# hand_pcb.net
KiCad netlist of a schematic drawn in EAGLE
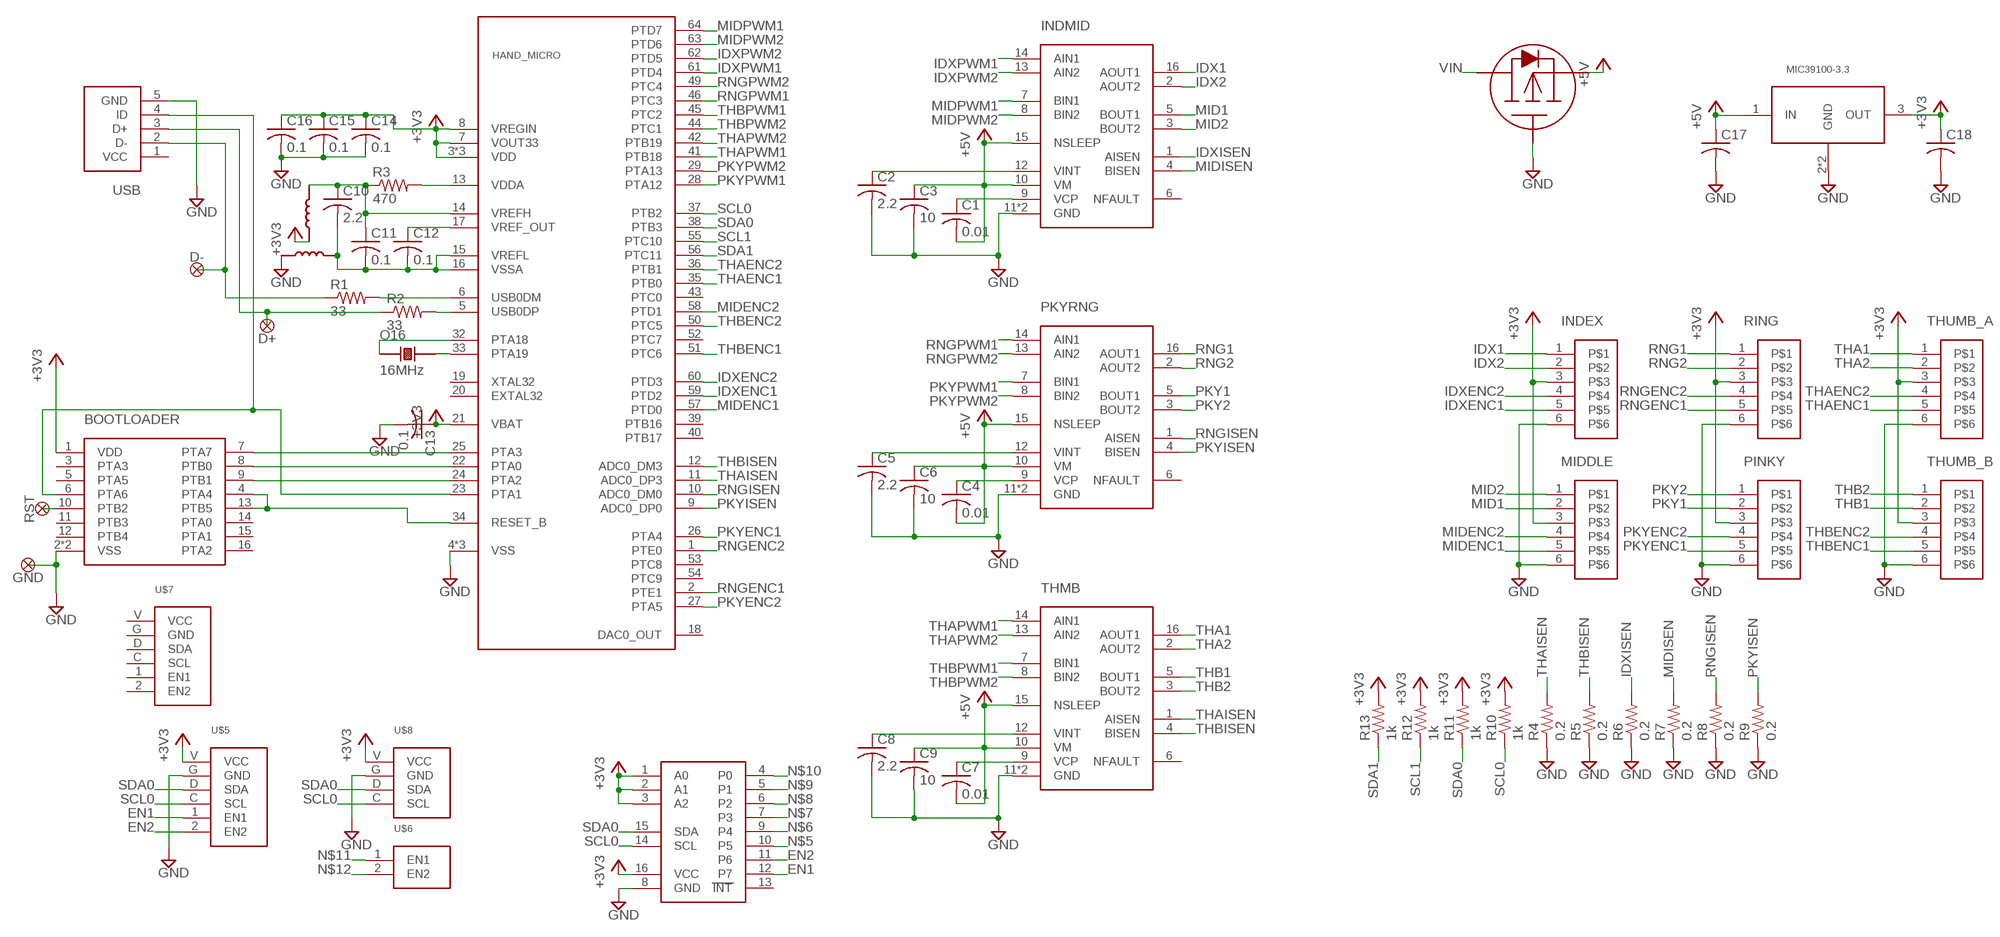
[diagram p0: schematic, sheet 1]

(export (version "E")
  (design (tool "Eeschema 10.0.6"))
  (components
    (comp (ref "BOOTLOADER")
      (value "MKL02Z32")
      (footprint "eagle-import:WQFN-16")
      (libsource (lib "eagle-import") (part "MKL02Z32"))
    )
    (comp (ref "C1")
      (value "0.01")
      (footprint "eagle-import:C0603")
      (libsource (lib "eagle-import") (part "C-USC0603"))
    )
    (comp (ref "C2")
      (value "2.2")
      (footprint "eagle-import:C0603")
      (libsource (lib "eagle-import") (part "C-USC0603"))
    )
    (comp (ref "C3")
      (value "10")
      (footprint "eagle-import:C0603")
      (libsource (lib "eagle-import") (part "C-USC0603"))
    )
    (comp (ref "C4")
      (value "0.01")
      (footprint "eagle-import:C0603")
      (libsource (lib "eagle-import") (part "C-USC0603"))
    )
    (comp (ref "C5")
      (value "2.2")
      (footprint "eagle-import:C0603")
      (libsource (lib "eagle-import") (part "C-USC0603"))
    )
    (comp (ref "C6")
      (value "10")
      (footprint "eagle-import:C0603")
      (libsource (lib "eagle-import") (part "C-USC0603"))
    )
    (comp (ref "C7")
      (value "0.01")
      (footprint "eagle-import:C0603")
      (libsource (lib "eagle-import") (part "C-USC0603"))
    )
    (comp (ref "C8")
      (value "2.2")
      (footprint "eagle-import:C0603")
      (libsource (lib "eagle-import") (part "C-USC0603"))
    )
    (comp (ref "C9")
      (value "10")
      (footprint "eagle-import:C0603")
      (libsource (lib "eagle-import") (part "C-USC0603"))
    )
    (comp (ref "C10")
      (value "2.2")
      (footprint "eagle-import:C0402")
      (libsource (lib "eagle-import") (part "C-USC0402"))
    )
    (comp (ref "C11")
      (value "0.1")
      (footprint "eagle-import:C0402")
      (libsource (lib "eagle-import") (part "C-USC0402"))
    )
    (comp (ref "C12")
      (value "0.1")
      (footprint "eagle-import:C0402")
      (libsource (lib "eagle-import") (part "C-USC0402"))
    )
    (comp (ref "C13")
      (value "0.1")
      (footprint "eagle-import:C0402")
      (libsource (lib "eagle-import") (part "C-USC0402"))
    )
    (comp (ref "C14")
      (value "0.1")
      (footprint "eagle-import:C0402")
      (libsource (lib "eagle-import") (part "C-USC0402"))
    )
    (comp (ref "C15")
      (value "0.1")
      (footprint "eagle-import:C0402")
      (libsource (lib "eagle-import") (part "C-USC0402"))
    )
    (comp (ref "C16")
      (value "0.1")
      (footprint "eagle-import:C0402")
      (libsource (lib "eagle-import") (part "C-USC0402"))
    )
    (comp (ref "C17")
      (value "C-USC0603")
      (footprint "eagle-import:C0603")
      (libsource (lib "eagle-import") (part "C-USC0603"))
    )
    (comp (ref "C18")
      (value "C-USC0603")
      (footprint "eagle-import:C0603")
      (libsource (lib "eagle-import") (part "C-USC0603"))
    )
    (comp (ref "D+")
      (value "TESTPAD")
      (footprint "eagle-import:TESTPAD")
      (libsource (lib "eagle-import") (part "TESTPAD"))
    )
    (comp (ref "D-")
      (value "TESTPAD")
      (footprint "eagle-import:TESTPAD")
      (libsource (lib "eagle-import") (part "TESTPAD"))
    )
    (comp (ref "GND")
      (value "TESTPAD")
      (footprint "eagle-import:TESTPAD")
      (libsource (lib "eagle-import") (part "TESTPAD"))
    )
    (comp (ref "HAND_MICRO")
      (value "MK20DX256VLH7")
      (footprint "eagle-import:LQFP-64-10-10")
      (libsource (lib "eagle-import") (part "MK20DX256VLH7"))
    )
    (comp (ref "INDEX")
      (value "DF57H-6PTOP")
      (footprint "eagle-import:DF57H-6P-TOP")
      (libsource (lib "eagle-import") (part "DF57H-6PTOP"))
    )
    (comp (ref "INDMID")
      (value "DRV8833")
      (footprint "eagle-import:WQFN-16")
      (libsource (lib "eagle-import") (part "DRV8833"))
    )
    (comp (ref "MIDDLE")
      (value "DF57H-6PTOP")
      (footprint "eagle-import:DF57H-6P-TOP")
      (libsource (lib "eagle-import") (part "DF57H-6PTOP"))
    )
    (comp (ref "O16")
      (value "16MHz")
      (footprint "eagle-import:NX3225SA")
      (libsource (lib "eagle-import") (part "NX3225SA"))
    )
    (comp (ref "PINKY")
      (value "DF57H-6PTOP")
      (footprint "eagle-import:DF57H-6P-TOP")
      (libsource (lib "eagle-import") (part "DF57H-6PTOP"))
    )
    (comp (ref "PKYRNG")
      (value "DRV8833")
      (footprint "eagle-import:WQFN-16")
      (libsource (lib "eagle-import") (part "DRV8833"))
    )
    (comp (ref "R1")
      (value "33")
      (footprint "eagle-import:R0402")
      (libsource (lib "eagle-import") (part "R-US_R0402"))
    )
    (comp (ref "R2")
      (value "33")
      (footprint "eagle-import:R0402")
      (libsource (lib "eagle-import") (part "R-US_R0402"))
    )
    (comp (ref "R3")
      (value "470")
      (footprint "eagle-import:R0402")
      (libsource (lib "eagle-import") (part "R-US_R0402"))
    )
    (comp (ref "R4")
      (value "0.2")
      (footprint "eagle-import:R1206")
      (libsource (lib "eagle-import") (part "R-US_R1206"))
    )
    (comp (ref "R5")
      (value "0.2")
      (footprint "eagle-import:R1206")
      (libsource (lib "eagle-import") (part "R-US_R1206"))
    )
    (comp (ref "R6")
      (value "0.2")
      (footprint "eagle-import:R1206")
      (libsource (lib "eagle-import") (part "R-US_R1206"))
    )
    (comp (ref "R7")
      (value "0.2")
      (footprint "eagle-import:R1206")
      (libsource (lib "eagle-import") (part "R-US_R1206"))
    )
    (comp (ref "R8")
      (value "0.2")
      (footprint "eagle-import:R1206")
      (libsource (lib "eagle-import") (part "R-US_R1206"))
    )
    (comp (ref "R9")
      (value "0.2")
      (footprint "eagle-import:R1206")
      (libsource (lib "eagle-import") (part "R-US_R1206"))
    )
    (comp (ref "R10")
      (value "1k")
      (footprint "eagle-import:R0603")
      (libsource (lib "eagle-import") (part "R-US_R0603"))
    )
    (comp (ref "R11")
      (value "1k")
      (footprint "eagle-import:R0603")
      (libsource (lib "eagle-import") (part "R-US_R0603"))
    )
    (comp (ref "R12")
      (value "1k")
      (footprint "eagle-import:R0603")
      (libsource (lib "eagle-import") (part "R-US_R0603"))
    )
    (comp (ref "R13")
      (value "1k")
      (footprint "eagle-import:R0603")
      (libsource (lib "eagle-import") (part "R-US_R0603"))
    )
    (comp (ref "RING")
      (value "DF57H-6PTOP")
      (footprint "eagle-import:DF57H-6P-TOP")
      (libsource (lib "eagle-import") (part "DF57H-6PTOP"))
    )
    (comp (ref "RST")
      (value "TESTPAD")
      (footprint "eagle-import:TESTPAD")
      (libsource (lib "eagle-import") (part "TESTPAD"))
    )
    (comp (ref "THMB")
      (value "DRV8833")
      (footprint "eagle-import:WQFN-16")
      (libsource (lib "eagle-import") (part "DRV8833"))
    )
    (comp (ref "THUMB_A")
      (value "DF57H-6PTOP")
      (footprint "eagle-import:DF57H-6P-TOP")
      (libsource (lib "eagle-import") (part "DF57H-6PTOP"))
    )
    (comp (ref "THUMB_B")
      (value "DF57H-6PTOP")
      (footprint "eagle-import:DF57H-6P-TOP")
      (libsource (lib "eagle-import") (part "DF57H-6PTOP"))
    )
    (comp (ref "U$1")
      (value "TCA9534TSSOP")
      (footprint "eagle-import:TSSOP16")
      (libsource (lib "eagle-import") (part "TCA9534TSSOP"))
    )
    (comp (ref "U$2")
      (value "SPD15P10PLG")
      (footprint "eagle-import:PG-TO-252-3")
      (libsource (lib "eagle-import") (part "SPD15P10PLG"))
    )
    (comp (ref "U$3")
      (value "FERRITE600OHM100MHZ")
      (footprint "eagle-import:L0603")
      (libsource (lib "eagle-import") (part "FERRITE600OHM100MHZ"))
    )
    (comp (ref "U$4")
      (value "FERRITE600OHM100MHZ")
      (footprint "eagle-import:L0603")
      (libsource (lib "eagle-import") (part "FERRITE600OHM100MHZ"))
    )
    (comp (ref "U$5")
      (value "PSENSE")
      (footprint "eagle-import:PSENSE")
      (libsource (lib "eagle-import") (part "PSENSE"))
    )
    (comp (ref "U$6")
      (value "PSENSE2")
      (footprint "eagle-import:PSENSE2")
      (libsource (lib "eagle-import") (part "PSENSE2"))
    )
    (comp (ref "U$7")
      (value "PSENSE")
      (footprint "eagle-import:PSENSE")
      (libsource (lib "eagle-import") (part "PSENSE"))
    )
    (comp (ref "U$8")
      (value "PSENSE4")
      (footprint "eagle-import:PSENSE4")
      (libsource (lib "eagle-import") (part "PSENSE4"))
    )
    (comp (ref "U$9")
      (value "MIC391003.3")
      (footprint "eagle-import:MIC39100")
      (libsource (lib "eagle-import") (part "MIC391003.3"))
    )
    (comp (ref "USB")
      (value "10118194-0001LF")
      (footprint "eagle-import:10118194-0001LF")
      (libsource (lib "eagle-import") (part "10118194-0001LF"))
    )
  )
  (nets
    (net (code "1") (name "+3V3") (class "Default")
      (node (ref "BOOTLOADER") (pin "1") (pinfunction "VDD_1") (pintype "bidirectional"))
      (node (ref "C13") (pin "1") (pinfunction "1_1") (pintype "passive"))
      (node (ref "C14") (pin "1") (pinfunction "1_1") (pintype "passive"))
      (node (ref "C15") (pin "1") (pinfunction "1_1") (pintype "passive"))
      (node (ref "C16") (pin "1") (pinfunction "1_1") (pintype "passive"))
      (node (ref "C18") (pin "1") (pinfunction "1_1") (pintype "passive"))
      (node (ref "HAND_MICRO") (pin "21") (pinfunction "VBAT_21") (pintype "bidirectional"))
      (node (ref "HAND_MICRO") (pin "3") (pinfunction "VDD_3") (pintype "bidirectional"))
      (node (ref "HAND_MICRO") (pin "30") (pinfunction "VDD_30") (pintype "bidirectional"))
      (node (ref "HAND_MICRO") (pin "48") (pinfunction "VDD_48") (pintype "bidirectional"))
      (node (ref "HAND_MICRO") (pin "7") (pinfunction "VOUT33_7") (pintype "bidirectional"))
      (node (ref "HAND_MICRO") (pin "8") (pinfunction "VREGIN_8") (pintype "bidirectional"))
      (node (ref "INDEX") (pin "3") (pinfunction "P$3_3") (pintype "bidirectional"))
      (node (ref "MIDDLE") (pin "3") (pinfunction "P$3_3") (pintype "bidirectional"))
      (node (ref "PINKY") (pin "3") (pinfunction "P$3_3") (pintype "bidirectional"))
      (node (ref "R10") (pin "2") (pinfunction "2_2") (pintype "passive"))
      (node (ref "R11") (pin "2") (pinfunction "2_2") (pintype "passive"))
      (node (ref "R12") (pin "2") (pinfunction "2_2") (pintype "passive"))
      (node (ref "R13") (pin "2") (pinfunction "2_2") (pintype "passive"))
      (node (ref "RING") (pin "3") (pinfunction "P$3_3") (pintype "bidirectional"))
      (node (ref "THUMB_A") (pin "3") (pinfunction "P$3_3") (pintype "bidirectional"))
      (node (ref "THUMB_B") (pin "3") (pinfunction "P$3_3") (pintype "bidirectional"))
      (node (ref "U$1") (pin "1") (pinfunction "A0_1") (pintype "bidirectional"))
      (node (ref "U$1") (pin "16") (pinfunction "VCC_16") (pintype "bidirectional"))
      (node (ref "U$1") (pin "2") (pinfunction "A1_2") (pintype "bidirectional"))
      (node (ref "U$1") (pin "3") (pinfunction "A2_3") (pintype "bidirectional"))
      (node (ref "U$4") (pin "1") (pinfunction "P$1_1") (pintype "bidirectional"))
      (node (ref "U$5") (pin "V") (pinfunction "VCC_V") (pintype "bidirectional"))
      (node (ref "U$8") (pin "V") (pinfunction "VCC_V") (pintype "bidirectional"))
      (node (ref "U$9") (pin "3") (pinfunction "OUT_3") (pintype "bidirectional"))
    )
    (net (code "2") (name "+5V") (class "Default")
      (node (ref "C1") (pin "2") (pinfunction "2_2") (pintype "passive"))
      (node (ref "C17") (pin "1") (pinfunction "1_1") (pintype "passive"))
      (node (ref "C3") (pin "1") (pinfunction "1_1") (pintype "passive"))
      (node (ref "C4") (pin "2") (pinfunction "2_2") (pintype "passive"))
      (node (ref "C6") (pin "1") (pinfunction "1_1") (pintype "passive"))
      (node (ref "C7") (pin "2") (pinfunction "2_2") (pintype "passive"))
      (node (ref "C9") (pin "1") (pinfunction "1_1") (pintype "passive"))
      (node (ref "INDMID") (pin "10") (pinfunction "VM_10") (pintype "bidirectional"))
      (node (ref "INDMID") (pin "15") (pinfunction "NSLEEP_15") (pintype "bidirectional"))
      (node (ref "PKYRNG") (pin "10") (pinfunction "VM_10") (pintype "bidirectional"))
      (node (ref "PKYRNG") (pin "15") (pinfunction "NSLEEP_15") (pintype "bidirectional"))
      (node (ref "THMB") (pin "10") (pinfunction "VM_10") (pintype "bidirectional"))
      (node (ref "THMB") (pin "15") (pinfunction "NSLEEP_15") (pintype "bidirectional"))
      (node (ref "U$2") (pin "3") (pinfunction "3_3") (pintype "bidirectional"))
      (node (ref "U$9") (pin "1") (pinfunction "IN_1") (pintype "bidirectional"))
    )
    (net (code "3") (name "/EN1") (class "Default")
      (node (ref "U$1") (pin "12") (pinfunction "P7_12") (pintype "bidirectional"))
      (node (ref "U$5") (pin "1") (pinfunction "EN1_1") (pintype "bidirectional"))
    )
    (net (code "4") (name "/EN2") (class "Default")
      (node (ref "U$1") (pin "11") (pinfunction "P6_11") (pintype "bidirectional"))
      (node (ref "U$5") (pin "2") (pinfunction "EN2_2") (pintype "bidirectional"))
    )
    (net (code "5") (name "/IDX1") (class "Default")
      (node (ref "INDEX") (pin "1") (pinfunction "P$1_1") (pintype "bidirectional"))
      (node (ref "INDMID") (pin "16") (pinfunction "AOUT1_16") (pintype "bidirectional"))
    )
    (net (code "6") (name "/IDX2") (class "Default")
      (node (ref "INDEX") (pin "2") (pinfunction "P$2_2") (pintype "bidirectional"))
      (node (ref "INDMID") (pin "2") (pinfunction "AOUT2_2") (pintype "bidirectional"))
    )
    (net (code "7") (name "/IDXENC1") (class "Default")
      (node (ref "HAND_MICRO") (pin "59") (pinfunction "PTD2_59") (pintype "bidirectional"))
      (node (ref "INDEX") (pin "5") (pinfunction "P$5_5") (pintype "bidirectional"))
    )
    (net (code "8") (name "/IDXENC2") (class "Default")
      (node (ref "HAND_MICRO") (pin "60") (pinfunction "PTD3_60") (pintype "bidirectional"))
      (node (ref "INDEX") (pin "4") (pinfunction "P$4_4") (pintype "bidirectional"))
    )
    (net (code "9") (name "/IDXISEN") (class "Default")
      (node (ref "INDMID") (pin "1") (pinfunction "AISEN_1") (pintype "bidirectional"))
      (node (ref "R6") (pin "2") (pinfunction "2_2") (pintype "passive"))
    )
    (net (code "10") (name "/IDXPWM1") (class "Default")
      (node (ref "HAND_MICRO") (pin "61") (pinfunction "PTD4_61") (pintype "bidirectional"))
      (node (ref "INDMID") (pin "14") (pinfunction "AIN1_14") (pintype "bidirectional"))
    )
    (net (code "11") (name "/IDXPWM2") (class "Default")
      (node (ref "HAND_MICRO") (pin "62") (pinfunction "PTD5_62") (pintype "bidirectional"))
      (node (ref "INDMID") (pin "13") (pinfunction "AIN2_13") (pintype "bidirectional"))
    )
    (net (code "12") (name "/MID1") (class "Default")
      (node (ref "INDMID") (pin "5") (pinfunction "BOUT1_5") (pintype "bidirectional"))
      (node (ref "MIDDLE") (pin "2") (pinfunction "P$2_2") (pintype "bidirectional"))
    )
    (net (code "13") (name "/MID2") (class "Default")
      (node (ref "INDMID") (pin "3") (pinfunction "BOUT2_3") (pintype "bidirectional"))
      (node (ref "MIDDLE") (pin "1") (pinfunction "P$1_1") (pintype "bidirectional"))
    )
    (net (code "14") (name "/MIDENC1") (class "Default")
      (node (ref "HAND_MICRO") (pin "57") (pinfunction "PTD0_57") (pintype "bidirectional"))
      (node (ref "MIDDLE") (pin "5") (pinfunction "P$5_5") (pintype "bidirectional"))
    )
    (net (code "15") (name "/MIDENC2") (class "Default")
      (node (ref "HAND_MICRO") (pin "58") (pinfunction "PTD1_58") (pintype "bidirectional"))
      (node (ref "MIDDLE") (pin "4") (pinfunction "P$4_4") (pintype "bidirectional"))
    )
    (net (code "16") (name "/MIDISEN") (class "Default")
      (node (ref "INDMID") (pin "4") (pinfunction "BISEN_4") (pintype "bidirectional"))
      (node (ref "R7") (pin "2") (pinfunction "2_2") (pintype "passive"))
    )
    (net (code "17") (name "/MIDPWM1") (class "Default")
      (node (ref "HAND_MICRO") (pin "64") (pinfunction "PTD7_64") (pintype "bidirectional"))
      (node (ref "INDMID") (pin "7") (pinfunction "BIN1_7") (pintype "bidirectional"))
    )
    (net (code "18") (name "/MIDPWM2") (class "Default")
      (node (ref "HAND_MICRO") (pin "63") (pinfunction "PTD6_63") (pintype "bidirectional"))
      (node (ref "INDMID") (pin "8") (pinfunction "BIN2_8") (pintype "bidirectional"))
    )
    (net (code "19") (name "/N$5") (class "Default")
      (node (ref "U$1") (pin "10") (pinfunction "P5_10") (pintype "bidirectional"))
    )
    (net (code "20") (name "/N$6") (class "Default")
      (node (ref "U$1") (pin "9") (pinfunction "P4_9") (pintype "bidirectional"))
    )
    (net (code "21") (name "/N$7") (class "Default")
      (node (ref "U$1") (pin "7") (pinfunction "P3_7") (pintype "bidirectional"))
    )
    (net (code "22") (name "/N$8") (class "Default")
      (node (ref "U$1") (pin "6") (pinfunction "P2_6") (pintype "bidirectional"))
    )
    (net (code "23") (name "/N$9") (class "Default")
      (node (ref "U$1") (pin "5") (pinfunction "P1_5") (pintype "bidirectional"))
    )
    (net (code "24") (name "/N$10") (class "Default")
      (node (ref "U$1") (pin "4") (pinfunction "P0_4") (pintype "bidirectional"))
    )
    (net (code "25") (name "/N$11") (class "Default")
      (node (ref "U$6") (pin "1") (pinfunction "EN1_1") (pintype "bidirectional"))
    )
    (net (code "26") (name "/N$12") (class "Default")
      (node (ref "U$6") (pin "2") (pinfunction "EN2_2") (pintype "bidirectional"))
    )
    (net (code "27") (name "/PKY1") (class "Default")
      (node (ref "PINKY") (pin "2") (pinfunction "P$2_2") (pintype "bidirectional"))
      (node (ref "PKYRNG") (pin "5") (pinfunction "BOUT1_5") (pintype "bidirectional"))
    )
    (net (code "28") (name "/PKY2") (class "Default")
      (node (ref "PINKY") (pin "1") (pinfunction "P$1_1") (pintype "bidirectional"))
      (node (ref "PKYRNG") (pin "3") (pinfunction "BOUT2_3") (pintype "bidirectional"))
    )
    (net (code "29") (name "/PKYENC1") (class "Default")
      (node (ref "HAND_MICRO") (pin "26") (pinfunction "PTA4_26") (pintype "bidirectional"))
      (node (ref "PINKY") (pin "5") (pinfunction "P$5_5") (pintype "bidirectional"))
    )
    (net (code "30") (name "/PKYENC2") (class "Default")
      (node (ref "HAND_MICRO") (pin "27") (pinfunction "PTA5_27") (pintype "bidirectional"))
      (node (ref "PINKY") (pin "4") (pinfunction "P$4_4") (pintype "bidirectional"))
    )
    (net (code "31") (name "/PKYISEN") (class "Default")
      (node (ref "HAND_MICRO") (pin "9") (pinfunction "ADC0_DP0_9") (pintype "bidirectional"))
      (node (ref "PKYRNG") (pin "4") (pinfunction "BISEN_4") (pintype "bidirectional"))
      (node (ref "R9") (pin "2") (pinfunction "2_2") (pintype "passive"))
    )
    (net (code "32") (name "/PKYPWM1") (class "Default")
      (node (ref "HAND_MICRO") (pin "28") (pinfunction "PTA12_28") (pintype "bidirectional"))
      (node (ref "PKYRNG") (pin "7") (pinfunction "BIN1_7") (pintype "bidirectional"))
    )
    (net (code "33") (name "/PKYPWM2") (class "Default")
      (node (ref "HAND_MICRO") (pin "29") (pinfunction "PTA13_29") (pintype "bidirectional"))
      (node (ref "PKYRNG") (pin "8") (pinfunction "BIN2_8") (pintype "bidirectional"))
    )
    (net (code "34") (name "/RNG1") (class "Default")
      (node (ref "PKYRNG") (pin "16") (pinfunction "AOUT1_16") (pintype "bidirectional"))
      (node (ref "RING") (pin "1") (pinfunction "P$1_1") (pintype "bidirectional"))
    )
    (net (code "35") (name "/RNG2") (class "Default")
      (node (ref "PKYRNG") (pin "2") (pinfunction "AOUT2_2") (pintype "bidirectional"))
      (node (ref "RING") (pin "2") (pinfunction "P$2_2") (pintype "bidirectional"))
    )
    (net (code "36") (name "/RNGENC1") (class "Default")
      (node (ref "HAND_MICRO") (pin "2") (pinfunction "PTE1_2") (pintype "bidirectional"))
      (node (ref "RING") (pin "5") (pinfunction "P$5_5") (pintype "bidirectional"))
    )
    (net (code "37") (name "/RNGENC2") (class "Default")
      (node (ref "HAND_MICRO") (pin "1") (pinfunction "PTE0_1") (pintype "bidirectional"))
      (node (ref "RING") (pin "4") (pinfunction "P$4_4") (pintype "bidirectional"))
    )
    (net (code "38") (name "/RNGISEN") (class "Default")
      (node (ref "HAND_MICRO") (pin "10") (pinfunction "ADC0_DM0_10") (pintype "bidirectional"))
      (node (ref "PKYRNG") (pin "1") (pinfunction "AISEN_1") (pintype "bidirectional"))
      (node (ref "R8") (pin "2") (pinfunction "2_2") (pintype "passive"))
    )
    (net (code "39") (name "/RNGPWM1") (class "Default")
      (node (ref "HAND_MICRO") (pin "46") (pinfunction "PTC3_46") (pintype "bidirectional"))
      (node (ref "PKYRNG") (pin "14") (pinfunction "AIN1_14") (pintype "bidirectional"))
    )
    (net (code "40") (name "/RNGPWM2") (class "Default")
      (node (ref "HAND_MICRO") (pin "49") (pinfunction "PTC4_49") (pintype "bidirectional"))
      (node (ref "PKYRNG") (pin "13") (pinfunction "AIN2_13") (pintype "bidirectional"))
    )
    (net (code "41") (name "/SCL0") (class "Default")
      (node (ref "HAND_MICRO") (pin "37") (pinfunction "PTB2_37") (pintype "bidirectional"))
      (node (ref "R10") (pin "1") (pinfunction "1_1") (pintype "passive"))
      (node (ref "U$1") (pin "14") (pinfunction "SCL_14") (pintype "bidirectional"))
      (node (ref "U$5") (pin "C") (pinfunction "SCL_C") (pintype "bidirectional"))
      (node (ref "U$8") (pin "C") (pinfunction "SCL_C") (pintype "bidirectional"))
    )
    (net (code "42") (name "/SCL1") (class "Default")
      (node (ref "HAND_MICRO") (pin "55") (pinfunction "PTC10_55") (pintype "bidirectional"))
      (node (ref "R12") (pin "1") (pinfunction "1_1") (pintype "passive"))
    )
    (net (code "43") (name "/SDA0") (class "Default")
      (node (ref "HAND_MICRO") (pin "38") (pinfunction "PTB3_38") (pintype "bidirectional"))
      (node (ref "R11") (pin "1") (pinfunction "1_1") (pintype "passive"))
      (node (ref "U$1") (pin "15") (pinfunction "SDA_15") (pintype "bidirectional"))
      (node (ref "U$5") (pin "D") (pinfunction "SDA_D") (pintype "bidirectional"))
      (node (ref "U$8") (pin "D") (pinfunction "SDA_D") (pintype "bidirectional"))
    )
    (net (code "44") (name "/SDA1") (class "Default")
      (node (ref "HAND_MICRO") (pin "56") (pinfunction "PTC11_56") (pintype "bidirectional"))
      (node (ref "R13") (pin "1") (pinfunction "1_1") (pintype "passive"))
    )
    (net (code "45") (name "/THA1") (class "Default")
      (node (ref "THMB") (pin "16") (pinfunction "AOUT1_16") (pintype "bidirectional"))
      (node (ref "THUMB_A") (pin "1") (pinfunction "P$1_1") (pintype "bidirectional"))
    )
    (net (code "46") (name "/THA2") (class "Default")
      (node (ref "THMB") (pin "2") (pinfunction "AOUT2_2") (pintype "bidirectional"))
      (node (ref "THUMB_A") (pin "2") (pinfunction "P$2_2") (pintype "bidirectional"))
    )
    (net (code "47") (name "/THAENC1") (class "Default")
      (node (ref "HAND_MICRO") (pin "35") (pinfunction "PTB0_35") (pintype "bidirectional"))
      (node (ref "THUMB_A") (pin "5") (pinfunction "P$5_5") (pintype "bidirectional"))
    )
    (net (code "48") (name "/THAENC2") (class "Default")
      (node (ref "HAND_MICRO") (pin "36") (pinfunction "PTB1_36") (pintype "bidirectional"))
      (node (ref "THUMB_A") (pin "4") (pinfunction "P$4_4") (pintype "bidirectional"))
    )
    (net (code "49") (name "/THAISEN") (class "Default")
      (node (ref "HAND_MICRO") (pin "11") (pinfunction "ADC0_DP3_11") (pintype "bidirectional"))
      (node (ref "R4") (pin "2") (pinfunction "2_2") (pintype "passive"))
      (node (ref "THMB") (pin "1") (pinfunction "AISEN_1") (pintype "bidirectional"))
    )
    (net (code "50") (name "/THAPWM1") (class "Default")
      (node (ref "HAND_MICRO") (pin "41") (pinfunction "PTB18_41") (pintype "bidirectional"))
      (node (ref "THMB") (pin "14") (pinfunction "AIN1_14") (pintype "bidirectional"))
    )
    (net (code "51") (name "/THAPWM2") (class "Default")
      (node (ref "HAND_MICRO") (pin "42") (pinfunction "PTB19_42") (pintype "bidirectional"))
      (node (ref "THMB") (pin "13") (pinfunction "AIN2_13") (pintype "bidirectional"))
    )
    (net (code "52") (name "/THB1") (class "Default")
      (node (ref "THMB") (pin "5") (pinfunction "BOUT1_5") (pintype "bidirectional"))
      (node (ref "THUMB_B") (pin "2") (pinfunction "P$2_2") (pintype "bidirectional"))
    )
    (net (code "53") (name "/THB2") (class "Default")
      (node (ref "THMB") (pin "3") (pinfunction "BOUT2_3") (pintype "bidirectional"))
      (node (ref "THUMB_B") (pin "1") (pinfunction "P$1_1") (pintype "bidirectional"))
    )
    (net (code "54") (name "/THBENC1") (class "Default")
      (node (ref "HAND_MICRO") (pin "51") (pinfunction "PTC6_51") (pintype "bidirectional"))
      (node (ref "THUMB_B") (pin "5") (pinfunction "P$5_5") (pintype "bidirectional"))
    )
    (net (code "55") (name "/THBENC2") (class "Default")
      (node (ref "HAND_MICRO") (pin "50") (pinfunction "PTC5_50") (pintype "bidirectional"))
      (node (ref "THUMB_B") (pin "4") (pinfunction "P$4_4") (pintype "bidirectional"))
    )
    (net (code "56") (name "/THBISEN") (class "Default")
      (node (ref "HAND_MICRO") (pin "12") (pinfunction "ADC0_DM3_12") (pintype "bidirectional"))
      (node (ref "R5") (pin "2") (pinfunction "2_2") (pintype "passive"))
      (node (ref "THMB") (pin "4") (pinfunction "BISEN_4") (pintype "bidirectional"))
    )
    (net (code "57") (name "/THBPWM1") (class "Default")
      (node (ref "HAND_MICRO") (pin "45") (pinfunction "PTC2_45") (pintype "bidirectional"))
      (node (ref "THMB") (pin "7") (pinfunction "BIN1_7") (pintype "bidirectional"))
    )
    (net (code "58") (name "/THBPWM2") (class "Default")
      (node (ref "HAND_MICRO") (pin "44") (pinfunction "PTC1_44") (pintype "bidirectional"))
      (node (ref "THMB") (pin "8") (pinfunction "BIN2_8") (pintype "bidirectional"))
    )
    (net (code "59") (name "/VIN") (class "Default")
      (node (ref "U$2") (pin "2") (pinfunction "2_2") (pintype "bidirectional"))
    )
    (net (code "60") (name "GND") (class "Default")
      (node (ref "BOOTLOADER") (pin "2") (pinfunction "VSS_2") (pintype "bidirectional"))
      (node (ref "BOOTLOADER") (pin "PPAD") (pinfunction "VSS_PPAD") (pintype "bidirectional"))
      (node (ref "C13") (pin "2") (pinfunction "2_2") (pintype "passive"))
      (node (ref "C14") (pin "2") (pinfunction "2_2") (pintype "passive"))
      (node (ref "C15") (pin "2") (pinfunction "2_2") (pintype "passive"))
      (node (ref "C16") (pin "2") (pinfunction "2_2") (pintype "passive"))
      (node (ref "C17") (pin "2") (pinfunction "2_2") (pintype "passive"))
      (node (ref "C18") (pin "2") (pinfunction "2_2") (pintype "passive"))
      (node (ref "C2") (pin "2") (pinfunction "2_2") (pintype "passive"))
      (node (ref "C3") (pin "2") (pinfunction "2_2") (pintype "passive"))
      (node (ref "C5") (pin "2") (pinfunction "2_2") (pintype "passive"))
      (node (ref "C6") (pin "2") (pinfunction "2_2") (pintype "passive"))
      (node (ref "C8") (pin "2") (pinfunction "2_2") (pintype "passive"))
      (node (ref "C9") (pin "2") (pinfunction "2_2") (pintype "passive"))
      (node (ref "GND") (pin "P$1") (pinfunction "P$1_P$1") (pintype "bidirectional"))
      (node (ref "HAND_MICRO") (pin "31") (pinfunction "VSS_31") (pintype "bidirectional"))
      (node (ref "HAND_MICRO") (pin "4") (pinfunction "VSS_4") (pintype "bidirectional"))
      (node (ref "HAND_MICRO") (pin "47") (pinfunction "VSS_47") (pintype "bidirectional"))
      (node (ref "INDEX") (pin "6") (pinfunction "P$6_6") (pintype "bidirectional"))
      (node (ref "INDMID") (pin "11") (pinfunction "GND_11") (pintype "bidirectional"))
      (node (ref "INDMID") (pin "PPAD") (pinfunction "GND_PPAD") (pintype "bidirectional"))
      (node (ref "MIDDLE") (pin "6") (pinfunction "P$6_6") (pintype "bidirectional"))
      (node (ref "PINKY") (pin "6") (pinfunction "P$6_6") (pintype "bidirectional"))
      (node (ref "PKYRNG") (pin "11") (pinfunction "GND_11") (pintype "bidirectional"))
      (node (ref "PKYRNG") (pin "PPAD") (pinfunction "GND_PPAD") (pintype "bidirectional"))
      (node (ref "R4") (pin "1") (pinfunction "1_1") (pintype "passive"))
      (node (ref "R5") (pin "1") (pinfunction "1_1") (pintype "passive"))
      (node (ref "R6") (pin "1") (pinfunction "1_1") (pintype "passive"))
      (node (ref "R7") (pin "1") (pinfunction "1_1") (pintype "passive"))
      (node (ref "R8") (pin "1") (pinfunction "1_1") (pintype "passive"))
      (node (ref "R9") (pin "1") (pinfunction "1_1") (pintype "passive"))
      (node (ref "RING") (pin "6") (pinfunction "P$6_6") (pintype "bidirectional"))
      (node (ref "THMB") (pin "11") (pinfunction "GND_11") (pintype "bidirectional"))
      (node (ref "THMB") (pin "PPAD") (pinfunction "GND_PPAD") (pintype "bidirectional"))
      (node (ref "THUMB_A") (pin "6") (pinfunction "P$6_6") (pintype "bidirectional"))
      (node (ref "THUMB_B") (pin "6") (pinfunction "P$6_6") (pintype "bidirectional"))
      (node (ref "U$1") (pin "8") (pinfunction "GND_8") (pintype "bidirectional"))
      (node (ref "U$2") (pin "1") (pinfunction "1_1") (pintype "bidirectional"))
      (node (ref "U$3") (pin "1") (pinfunction "P$1_1") (pintype "bidirectional"))
      (node (ref "U$5") (pin "G") (pinfunction "GND_G") (pintype "bidirectional"))
      (node (ref "U$8") (pin "G") (pinfunction "GND_G") (pintype "bidirectional"))
      (node (ref "U$9") (pin "2") (pinfunction "GND_2") (pintype "bidirectional"))
      (node (ref "U$9") (pin "TAB") (pinfunction "GND_TAB") (pintype "bidirectional"))
      (node (ref "USB") (pin "5") (pinfunction "GND_5") (pintype "bidirectional"))
    )
    (net (code "61") (name "Net-(BOOTLOADER-PTA4)") (class "Default")
      (node (ref "BOOTLOADER") (pin "13") (pinfunction "PTB5_13") (pintype "bidirectional"))
      (node (ref "BOOTLOADER") (pin "4") (pinfunction "PTA4_4") (pintype "bidirectional"))
      (node (ref "HAND_MICRO") (pin "34") (pinfunction "RESET_B_34") (pintype "bidirectional"))
    )
    (net (code "62") (name "Net-(BOOTLOADER-PTA6)") (class "Default")
      (node (ref "BOOTLOADER") (pin "6") (pinfunction "PTA6_6") (pintype "bidirectional"))
      (node (ref "HAND_MICRO") (pin "23") (pinfunction "PTA1_23") (pintype "bidirectional"))
      (node (ref "USB") (pin "4") (pinfunction "ID_4") (pintype "bidirectional"))
    )
    (net (code "63") (name "Net-(BOOTLOADER-PTA7)") (class "Default")
      (node (ref "BOOTLOADER") (pin "7") (pinfunction "PTA7_7") (pintype "bidirectional"))
      (node (ref "HAND_MICRO") (pin "25") (pinfunction "PTA3_25") (pintype "bidirectional"))
    )
    (net (code "64") (name "Net-(BOOTLOADER-PTB0)") (class "Default")
      (node (ref "BOOTLOADER") (pin "8") (pinfunction "PTB0_8") (pintype "bidirectional"))
      (node (ref "HAND_MICRO") (pin "22") (pinfunction "PTA0_22") (pintype "bidirectional"))
    )
    (net (code "65") (name "Net-(BOOTLOADER-PTB1)") (class "Default")
      (node (ref "BOOTLOADER") (pin "9") (pinfunction "PTB1_9") (pintype "bidirectional"))
      (node (ref "HAND_MICRO") (pin "24") (pinfunction "PTA2_24") (pintype "bidirectional"))
    )
    (net (code "66") (name "Net-(BOOTLOADER-PTB2)") (class "Default")
      (node (ref "BOOTLOADER") (pin "10") (pinfunction "PTB2_10") (pintype "bidirectional"))
      (node (ref "RST") (pin "P$1") (pinfunction "P$1_P$1") (pintype "bidirectional"))
    )
    (net (code "67") (name "Net-(HAND_MICRO-PTA18)") (class "Default")
      (node (ref "HAND_MICRO") (pin "32") (pinfunction "PTA18_32") (pintype "bidirectional"))
      (node (ref "O16") (pin "1") (pinfunction "P$1_1") (pintype "bidirectional"))
    )
    (net (code "68") (name "Net-(HAND_MICRO-PTA19)") (class "Default")
      (node (ref "HAND_MICRO") (pin "33") (pinfunction "PTA19_33") (pintype "bidirectional"))
      (node (ref "O16") (pin "3") (pinfunction "P$2_3") (pintype "bidirectional"))
    )
    (net (code "69") (name "Net-(HAND_MICRO-USB0DM)") (class "Default")
      (node (ref "HAND_MICRO") (pin "6") (pinfunction "USB0DM_6") (pintype "bidirectional"))
      (node (ref "R1") (pin "2") (pinfunction "2_2") (pintype "passive"))
    )
    (net (code "70") (name "Net-(HAND_MICRO-USB0DP)") (class "Default")
      (node (ref "HAND_MICRO") (pin "5") (pinfunction "USB0DP_5") (pintype "bidirectional"))
      (node (ref "R2") (pin "2") (pinfunction "2_2") (pintype "passive"))
    )
    (net (code "71") (name "Net-(HAND_MICRO-VDDA)") (class "Default")
      (node (ref "HAND_MICRO") (pin "13") (pinfunction "VDDA_13") (pintype "bidirectional"))
      (node (ref "R3") (pin "2") (pinfunction "2_2") (pintype "passive"))
    )
    (net (code "72") (name "Net-(HAND_MICRO-VREFH)") (class "Default")
      (node (ref "C10") (pin "1") (pinfunction "1_1") (pintype "passive"))
      (node (ref "C11") (pin "1") (pinfunction "1_1") (pintype "passive"))
      (node (ref "HAND_MICRO") (pin "14") (pinfunction "VREFH_14") (pintype "bidirectional"))
      (node (ref "R3") (pin "1") (pinfunction "1_1") (pintype "passive"))
      (node (ref "U$4") (pin "2") (pinfunction "P$2_2") (pintype "bidirectional"))
    )
    (net (code "73") (name "Net-(HAND_MICRO-VREFL)") (class "Default")
      (node (ref "C10") (pin "2") (pinfunction "2_2") (pintype "passive"))
      (node (ref "C11") (pin "2") (pinfunction "2_2") (pintype "passive"))
      (node (ref "C12") (pin "2") (pinfunction "2_2") (pintype "passive"))
      (node (ref "HAND_MICRO") (pin "15") (pinfunction "VREFL_15") (pintype "bidirectional"))
      (node (ref "HAND_MICRO") (pin "16") (pinfunction "VSSA_16") (pintype "bidirectional"))
      (node (ref "U$3") (pin "2") (pinfunction "P$2_2") (pintype "bidirectional"))
    )
    (net (code "74") (name "Net-(HAND_MICRO-VREF_OUT)") (class "Default")
      (node (ref "C12") (pin "1") (pinfunction "1_1") (pintype "passive"))
      (node (ref "HAND_MICRO") (pin "17") (pinfunction "VREF_OUT_17") (pintype "bidirectional"))
    )
    (net (code "75") (name "Net-(INDMID-VCP)") (class "Default")
      (node (ref "C1") (pin "1") (pinfunction "1_1") (pintype "passive"))
      (node (ref "INDMID") (pin "9") (pinfunction "VCP_9") (pintype "bidirectional"))
    )
    (net (code "76") (name "Net-(INDMID-VINT)") (class "Default")
      (node (ref "C2") (pin "1") (pinfunction "1_1") (pintype "passive"))
      (node (ref "INDMID") (pin "12") (pinfunction "VINT_12") (pintype "bidirectional"))
    )
    (net (code "77") (name "Net-(PKYRNG-VCP)") (class "Default")
      (node (ref "C4") (pin "1") (pinfunction "1_1") (pintype "passive"))
      (node (ref "PKYRNG") (pin "9") (pinfunction "VCP_9") (pintype "bidirectional"))
    )
    (net (code "78") (name "Net-(PKYRNG-VINT)") (class "Default")
      (node (ref "C5") (pin "1") (pinfunction "1_1") (pintype "passive"))
      (node (ref "PKYRNG") (pin "12") (pinfunction "VINT_12") (pintype "bidirectional"))
    )
    (net (code "79") (name "Net-(THMB-VCP)") (class "Default")
      (node (ref "C7") (pin "1") (pinfunction "1_1") (pintype "passive"))
      (node (ref "THMB") (pin "9") (pinfunction "VCP_9") (pintype "bidirectional"))
    )
    (net (code "80") (name "Net-(THMB-VINT)") (class "Default")
      (node (ref "C8") (pin "1") (pinfunction "1_1") (pintype "passive"))
      (node (ref "THMB") (pin "12") (pinfunction "VINT_12") (pintype "bidirectional"))
    )
    (net (code "81") (name "Net-(USB-D+)") (class "Default")
      (node (ref "D+") (pin "P$1") (pinfunction "P$1_P$1") (pintype "bidirectional"))
      (node (ref "R2") (pin "1") (pinfunction "1_1") (pintype "passive"))
      (node (ref "USB") (pin "3") (pinfunction "D+_3") (pintype "bidirectional"))
    )
    (net (code "82") (name "Net-(USB-D-)") (class "Default")
      (node (ref "D-") (pin "P$1") (pinfunction "P$1_P$1") (pintype "bidirectional"))
      (node (ref "R1") (pin "1") (pinfunction "1_1") (pintype "passive"))
      (node (ref "USB") (pin "2") (pinfunction "D-_2") (pintype "bidirectional"))
    )
    (net (code "83") (name "unconnected-(BOOTLOADER-PTA0-Pad14)") (class "Default")
      (node (ref "BOOTLOADER") (pin "14") (pinfunction "PTA0_14") (pintype "bidirectional"))
    )
    (net (code "84") (name "unconnected-(BOOTLOADER-PTA1-Pad15)") (class "Default")
      (node (ref "BOOTLOADER") (pin "15") (pinfunction "PTA1_15") (pintype "bidirectional"))
    )
    (net (code "85") (name "unconnected-(BOOTLOADER-PTA2-Pad16)") (class "Default")
      (node (ref "BOOTLOADER") (pin "16") (pinfunction "PTA2_16") (pintype "bidirectional"))
    )
    (net (code "86") (name "unconnected-(BOOTLOADER-PTA3-Pad3)") (class "Default")
      (node (ref "BOOTLOADER") (pin "3") (pinfunction "PTA3_3") (pintype "bidirectional"))
    )
    (net (code "87") (name "unconnected-(BOOTLOADER-PTA5-Pad5)") (class "Default")
      (node (ref "BOOTLOADER") (pin "5") (pinfunction "PTA5_5") (pintype "bidirectional"))
    )
    (net (code "88") (name "unconnected-(BOOTLOADER-PTB3-Pad11)") (class "Default")
      (node (ref "BOOTLOADER") (pin "11") (pinfunction "PTB3_11") (pintype "bidirectional"))
    )
    (net (code "89") (name "unconnected-(BOOTLOADER-PTB4-Pad12)") (class "Default")
      (node (ref "BOOTLOADER") (pin "12") (pinfunction "PTB4_12") (pintype "bidirectional"))
    )
    (net (code "90") (name "unconnected-(HAND_MICRO-DAC0_OUT-Pad18)") (class "Default")
      (node (ref "HAND_MICRO") (pin "18") (pinfunction "DAC0_OUT_18") (pintype "bidirectional"))
    )
    (net (code "91") (name "unconnected-(HAND_MICRO-EXTAL32-Pad20)") (class "Default")
      (node (ref "HAND_MICRO") (pin "20") (pinfunction "EXTAL32_20") (pintype "bidirectional"))
    )
    (net (code "92") (name "unconnected-(HAND_MICRO-PTB16-Pad39)") (class "Default")
      (node (ref "HAND_MICRO") (pin "39") (pinfunction "PTB16_39") (pintype "bidirectional"))
    )
    (net (code "93") (name "unconnected-(HAND_MICRO-PTB17-Pad40)") (class "Default")
      (node (ref "HAND_MICRO") (pin "40") (pinfunction "PTB17_40") (pintype "bidirectional"))
    )
    (net (code "94") (name "unconnected-(HAND_MICRO-PTC0-Pad43)") (class "Default")
      (node (ref "HAND_MICRO") (pin "43") (pinfunction "PTC0_43") (pintype "bidirectional"))
    )
    (net (code "95") (name "unconnected-(HAND_MICRO-PTC7-Pad52)") (class "Default")
      (node (ref "HAND_MICRO") (pin "52") (pinfunction "PTC7_52") (pintype "bidirectional"))
    )
    (net (code "96") (name "unconnected-(HAND_MICRO-PTC8-Pad53)") (class "Default")
      (node (ref "HAND_MICRO") (pin "53") (pinfunction "PTC8_53") (pintype "bidirectional"))
    )
    (net (code "97") (name "unconnected-(HAND_MICRO-PTC9-Pad54)") (class "Default")
      (node (ref "HAND_MICRO") (pin "54") (pinfunction "PTC9_54") (pintype "bidirectional"))
    )
    (net (code "98") (name "unconnected-(HAND_MICRO-XTAL32-Pad19)") (class "Default")
      (node (ref "HAND_MICRO") (pin "19") (pinfunction "XTAL32_19") (pintype "bidirectional"))
    )
    (net (code "99") (name "unconnected-(INDMID-NFAULT-Pad6)") (class "Default")
      (node (ref "INDMID") (pin "6") (pinfunction "NFAULT_6") (pintype "bidirectional"))
    )
    (net (code "100") (name "unconnected-(PKYRNG-NFAULT-Pad6)") (class "Default")
      (node (ref "PKYRNG") (pin "6") (pinfunction "NFAULT_6") (pintype "bidirectional"))
    )
    (net (code "101") (name "unconnected-(THMB-NFAULT-Pad6)") (class "Default")
      (node (ref "THMB") (pin "6") (pinfunction "NFAULT_6") (pintype "bidirectional"))
    )
    (net (code "102") (name "unconnected-(U$1-INT-Pad13)") (class "Default")
      (node (ref "U$1") (pin "13") (pinfunction "INT_13") (pintype "bidirectional"))
    )
    (net (code "103") (name "unconnected-(U$7-EN1-Pad1)") (class "Default")
      (node (ref "U$7") (pin "1") (pinfunction "EN1_1") (pintype "bidirectional"))
    )
    (net (code "104") (name "unconnected-(U$7-EN2-Pad2)") (class "Default")
      (node (ref "U$7") (pin "2") (pinfunction "EN2_2") (pintype "bidirectional"))
    )
    (net (code "105") (name "unconnected-(U$7-GND-PadG)") (class "Default")
      (node (ref "U$7") (pin "G") (pinfunction "GND_G") (pintype "bidirectional"))
    )
    (net (code "106") (name "unconnected-(U$7-SCL-PadC)") (class "Default")
      (node (ref "U$7") (pin "C") (pinfunction "SCL_C") (pintype "bidirectional"))
    )
    (net (code "107") (name "unconnected-(U$7-SDA-PadD)") (class "Default")
      (node (ref "U$7") (pin "D") (pinfunction "SDA_D") (pintype "bidirectional"))
    )
    (net (code "108") (name "unconnected-(U$7-VCC-PadV)") (class "Default")
      (node (ref "U$7") (pin "V") (pinfunction "VCC_V") (pintype "bidirectional"))
    )
    (net (code "109") (name "unconnected-(USB-VCC-Pad1)") (class "Default")
      (node (ref "USB") (pin "1") (pinfunction "VCC_1") (pintype "bidirectional"))
    )
  )
)
